# TemperatureACQ.net
KiCad netlist of a schematic drawn in Altium Designer
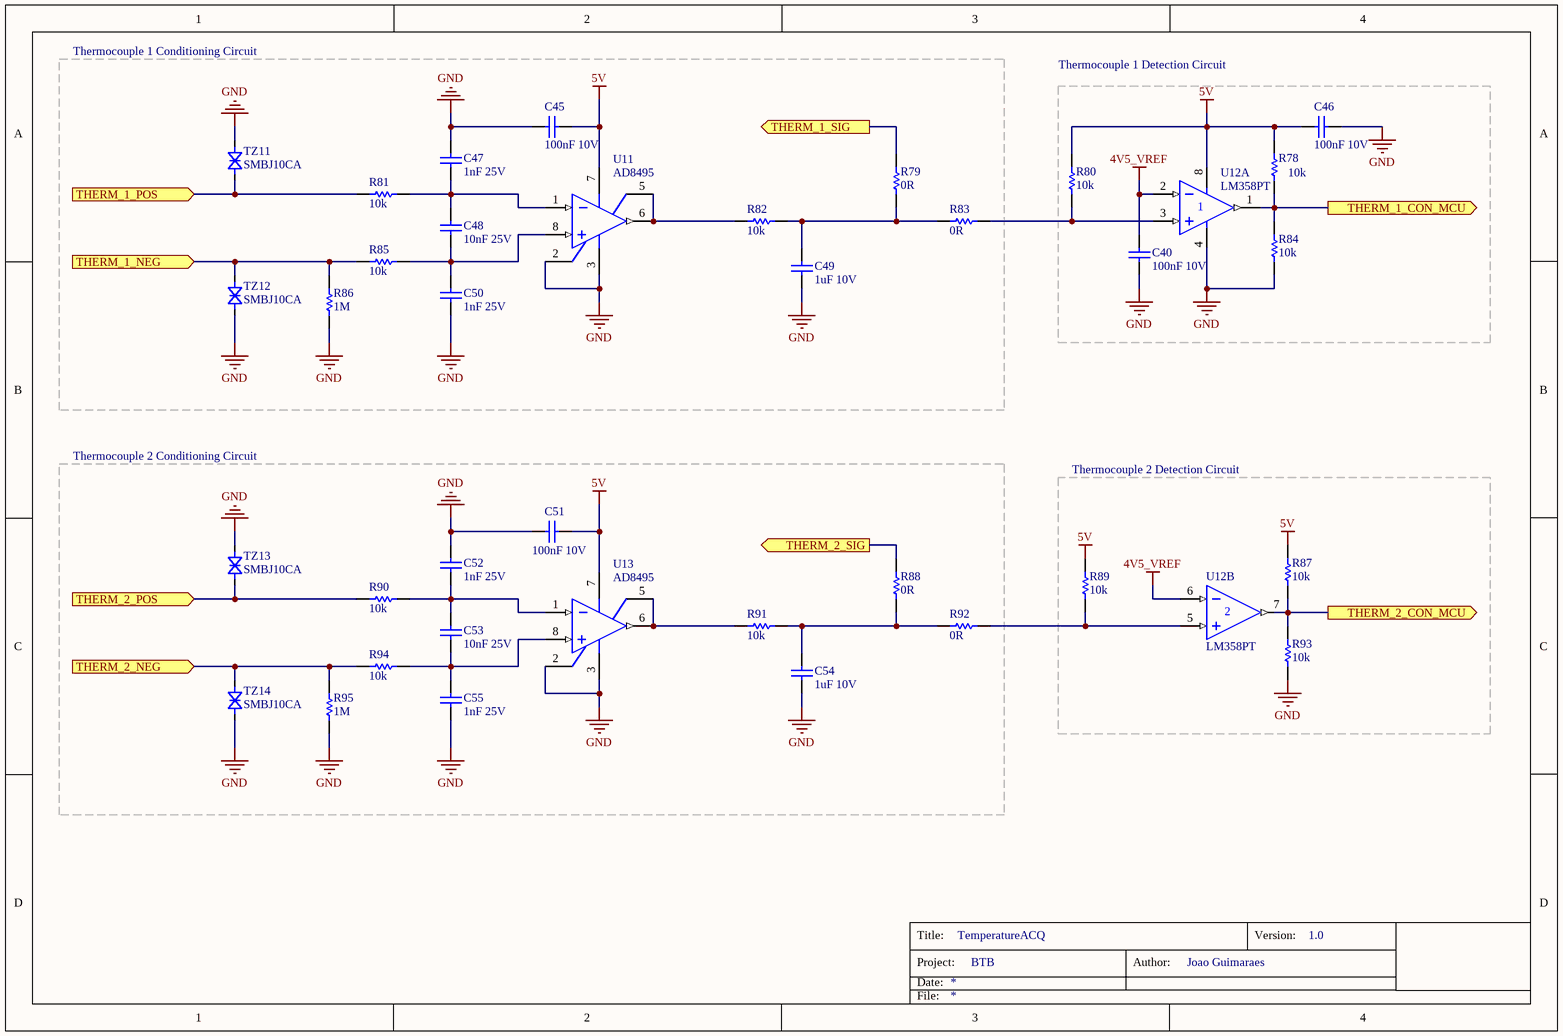
[diagram p0: TemperatureACQ.SchDoc]

(export (version "E")
  (design (tool "Eeschema 10.0.6"))
  (components
    (comp (ref "C40")
      (value "100nF 10V")
      (footprint "0402")
      (description "Capacitor")
      (fields (field (name "PARTNUMBER") "CAP.100n.10V.20%.SMD.0402") (field (name "MANUFACTURER") "Wurth"))
      (libsource (lib "IntLib") (part "Cap"))
    )
    (comp (ref "C45")
      (value "100nF 10V")
      (footprint "0402")
      (description "Capacitor")
      (fields (field (name "PARTNUMBER") "CAP.100n.10V.20%.SMD.0402") (field (name "MANUFACTURER") "Wurth"))
      (libsource (lib "IntLib") (part "Cap"))
    )
    (comp (ref "C46")
      (value "100nF 10V")
      (footprint "0402")
      (description "Capacitor")
      (fields (field (name "PARTNUMBER") "CAP.100n.10V.20%.SMD.0402") (field (name "MANUFACTURER") "Wurth"))
      (libsource (lib "IntLib") (part "Cap"))
    )
    (comp (ref "C47")
      (value "1nF 25V")
      (footprint "1608[0603]")
      (description "Capacitor")
      (fields (field (name "PARTNUMBER") "CAP.1n.25V.10%.SMD.0603") (field (name "MANUFACTURER") "Wurth"))
      (libsource (lib "IntLib") (part "Cap"))
    )
    (comp (ref "C48")
      (value "10nF 25V")
      (footprint "1608[0603]")
      (description "Capacitor")
      (fields (field (name "PARTNUMBER") "CAP.10n.25V.10%.SMD.0603") (field (name "MANUFACTURER") "Wurth"))
      (libsource (lib "IntLib") (part "Cap"))
    )
    (comp (ref "C49")
      (value "1uF 10V")
      (footprint "C0805")
      (description "Capacitor")
      (fields (field (name "PARTNUMBER") "CAP.1u.10V.10%.SMD.0805") (field (name "MANUFACTURER") "Vishay"))
      (libsource (lib "IntLib") (part "Cap"))
    )
    (comp (ref "C50")
      (value "1nF 25V")
      (footprint "1608[0603]")
      (description "Capacitor")
      (fields (field (name "PARTNUMBER") "CAP.1n.25V.10%.SMD.0603") (field (name "MANUFACTURER") "Vishay"))
      (libsource (lib "IntLib") (part "Cap"))
    )
    (comp (ref "C51")
      (value "100nF 10V")
      (footprint "0402")
      (description "Capacitor")
      (fields (field (name "PARTNUMBER") "CAP.100n.10V.20%.SMD.0402") (field (name "MANUFACTURER") "Wurth"))
      (libsource (lib "IntLib") (part "Cap"))
    )
    (comp (ref "C52")
      (value "1nF 25V")
      (footprint "1608[0603]")
      (description "Capacitor")
      (fields (field (name "PARTNUMBER") "CAP.1n.25V.10%.SMD.0603") (field (name "MANUFACTURER") "Vishay"))
      (libsource (lib "IntLib") (part "Cap"))
    )
    (comp (ref "C53")
      (value "10nF 25V")
      (footprint "1608[0603]")
      (description "Capacitor")
      (fields (field (name "PARTNUMBER") "CAP.10n.25V.10%.SMD.0603") (field (name "MANUFACTURER") "Wurth"))
      (libsource (lib "IntLib") (part "Cap"))
    )
    (comp (ref "C54")
      (value "1uF 10V")
      (footprint "C0805")
      (description "Capacitor")
      (fields (field (name "PARTNUMBER") "CAP.1u.10V.10%.SMD.0805") (field (name "MANUFACTURER") "Vishay"))
      (libsource (lib "IntLib") (part "Cap"))
    )
    (comp (ref "C55")
      (value "1nF 25V")
      (footprint "1608[0603]")
      (description "Capacitor")
      (fields (field (name "PARTNUMBER") "CAP.1n.25V.10%.SMD.0603") (field (name "MANUFACTURER") "Wurth"))
      (libsource (lib "IntLib") (part "Cap"))
    )
    (comp (ref "R78")
      (value "10k")
      (footprint "6-0805_M")
      (description "Resistor")
      (fields (field (name "PARTNUMBER") "RES.10K.1/8W.5%.SMD.0805") (field (name "MANUFACTURER") "Yageo"))
      (libsource (lib "IntLib") (part "Res"))
    )
    (comp (ref "R79")
      (value "0R")
      (footprint "6-0805_M")
      (description "Resistor")
      (fields (field (name "PARTNUMBER") "RES.0R.1/8W.5%.SMD.0805") (field (name "MANUFACTURER") "Vishay"))
      (libsource (lib "IntLib") (part "Res"))
    )
    (comp (ref "R80")
      (value "10k")
      (footprint "6-0805_M")
      (description "Resistor")
      (fields (field (name "PARTNUMBER") "RES.10k.1/8W.5%.SMD.0805") (field (name "MANUFACTURER") "Bourns"))
      (libsource (lib "IntLib") (part "Res"))
    )
    (comp (ref "R81")
      (value "10k")
      (footprint "6-0805_M")
      (description "Resistor")
      (fields (field (name "PARTNUMBER") "RES.10K.1/8W.5%.SMD.0805") (field (name "MANUFACTURER") "Yageo"))
      (libsource (lib "IntLib") (part "Res"))
    )
    (comp (ref "R82")
      (value "10k")
      (footprint "6-0805_M")
      (description "Resistor")
      (fields (field (name "PARTNUMBER") "RES.10K.1/8W.5%.SMD.0805") (field (name "MANUFACTURER") "Yageo"))
      (libsource (lib "IntLib") (part "Res"))
    )
    (comp (ref "R83")
      (value "0R")
      (footprint "6-0805_M")
      (description "Resistor")
      (fields (field (name "PARTNUMBER") "RES.0R.1/8W.5%.SMD.0805") (field (name "MANUFACTURER") "Vishay"))
      (libsource (lib "IntLib") (part "Res"))
    )
    (comp (ref "R84")
      (value "10k")
      (footprint "6-0805_M")
      (description "Resistor")
      (fields (field (name "PARTNUMBER") "RES.10K.1/8W.5%.SMD.0805") (field (name "MANUFACTURER") "Yageo"))
      (libsource (lib "IntLib") (part "Res"))
    )
    (comp (ref "R85")
      (value "10k")
      (footprint "6-0805_M")
      (description "Resistor")
      (fields (field (name "PARTNUMBER") "RES.10K.1/8W.5%.SMD.0805") (field (name "MANUFACTURER") "Yageo"))
      (libsource (lib "IntLib") (part "Res"))
    )
    (comp (ref "R86")
      (value "1M")
      (footprint "6-0805_M")
      (description "Resistor")
      (fields (field (name "PARTNUMBER") "RES.1M.1/8W.5%.SMD.0805") (field (name "MANUFACTURER") "Bourns"))
      (libsource (lib "IntLib") (part "Res"))
    )
    (comp (ref "R87")
      (value "10k")
      (footprint "6-0805_M")
      (description "Resistor")
      (fields (field (name "PARTNUMBER") "RES.10K.1/8W.5%.SMD.0805") (field (name "MANUFACTURER") "Yageo"))
      (libsource (lib "IntLib") (part "Res"))
    )
    (comp (ref "R88")
      (value "0R")
      (footprint "6-0805_M")
      (description "Resistor")
      (fields (field (name "PARTNUMBER") "RES.0R.1/8W.5%.SMD.0805") (field (name "MANUFACTURER") "Vishay"))
      (libsource (lib "IntLib") (part "Res"))
    )
    (comp (ref "R89")
      (value "10k")
      (footprint "6-0805_M")
      (description "Resistor")
      (fields (field (name "PARTNUMBER") "RES.10k.1/8W.5%.SMD.0805") (field (name "MANUFACTURER") "Bourns"))
      (libsource (lib "IntLib") (part "Res"))
    )
    (comp (ref "R90")
      (value "10k")
      (footprint "6-0805_M")
      (description "Resistor")
      (fields (field (name "PARTNUMBER") "RES.10K.1/8W.5%.SMD.0805") (field (name "MANUFACTURER") "Yageo"))
      (libsource (lib "IntLib") (part "Res"))
    )
    (comp (ref "R91")
      (value "10k")
      (footprint "6-0805_M")
      (description "Resistor")
      (fields (field (name "PARTNUMBER") "RES.10K.1/8W.5%.SMD.0805") (field (name "MANUFACTURER") "Yageo"))
      (libsource (lib "IntLib") (part "Res"))
    )
    (comp (ref "R92")
      (value "0R")
      (footprint "6-0805_M")
      (description "Resistor")
      (fields (field (name "PARTNUMBER") "RES.0R.1/8W.5%.SMD.0805") (field (name "MANUFACTURER") "Vishay"))
      (libsource (lib "IntLib") (part "Res"))
    )
    (comp (ref "R93")
      (value "10k")
      (footprint "6-0805_M")
      (description "Resistor")
      (fields (field (name "PARTNUMBER") "RES.10K.1/8W.5%.SMD.0805") (field (name "MANUFACTURER") "Yageo"))
      (libsource (lib "IntLib") (part "Res"))
    )
    (comp (ref "R94")
      (value "10k")
      (footprint "6-0805_M")
      (description "Resistor")
      (fields (field (name "PARTNUMBER") "RES.10K.1/8W.5%.SMD.0805") (field (name "MANUFACTURER") "Yageo"))
      (libsource (lib "IntLib") (part "Res"))
    )
    (comp (ref "R95")
      (value "1M")
      (footprint "6-0805_M")
      (description "Resistor")
      (fields (field (name "PARTNUMBER") "RES.1M.1/8W.5%.SMD.0805") (field (name "MANUFACTURER") "Bourns"))
      (libsource (lib "IntLib") (part "Res"))
    )
    (comp (ref "TZ11")
      (value "SMBJ10CA")
      (footprint "DO-214AA")
      (description "ESD Suppressors / TVS Diodes 600W 10.0V")
      (fields (field (name "PARTNUMBER") "SMBJ10CA-13-F") (field (name "MANUFACTURER") "Diodes"))
      (libsource (lib "IntLib") (part "SMBJ10CA"))
    )
    (comp (ref "TZ12")
      (value "SMBJ10CA")
      (footprint "DO-214AA")
      (description "ESD Suppressors / TVS Diodes 600W 10.0V")
      (fields (field (name "PARTNUMBER") "SMBJ10CA-13-F") (field (name "MANUFACTURER") "Diodes"))
      (libsource (lib "IntLib") (part "SMBJ10CA"))
    )
    (comp (ref "TZ13")
      (value "SMBJ10CA")
      (footprint "DO-214AA")
      (description "ESD Suppressors / TVS Diodes 600W 10.0V")
      (fields (field (name "PARTNUMBER") "SMBJ10CA-13-F") (field (name "MANUFACTURER") "Diodes"))
      (libsource (lib "IntLib") (part "SMBJ10CA"))
    )
    (comp (ref "TZ14")
      (value "SMBJ10CA")
      (footprint "DO-214AA")
      (description "ESD Suppressors / TVS Diodes 600W 10.0V")
      (fields (field (name "PARTNUMBER") "SMBJ10CA-13-F") (field (name "MANUFACTURER") "Diodes"))
      (libsource (lib "IntLib") (part "SMBJ10CA"))
    )
    (comp (ref "U11")
      (value "AD8495")
      (footprint "RM_8")
      (description "Precision Type K Thermocouple Amplifier with Cold Junction Compensation")
      (fields (field (name "PARTNUMBER") "AD8495CRMZ-R7") (field (name "MANUFACTURER") "Analog Devices"))
      (libsource (lib "IntLib") (part "AD8495"))
    )
    (comp (ref "U12")
      (value "LM358PT")
      (footprint "TSOP-8")
      (description "Operational Amplifiers - Op Amps Dual Low Power")
      (fields (field (name "MANUFACTURER") "STMicroelectronics"))
      (libsource (lib "IntLib") (part "LM358PT"))
    )
    (comp (ref "U13")
      (value "AD8495")
      (footprint "RM_8")
      (description "Precision Type K Thermocouple Amplifier with Cold Junction Compensation")
      (fields (field (name "PARTNUMBER") "AD8495CRMZ-R7") (field (name "MANUFACTURER") "Analog Devices"))
      (libsource (lib "IntLib") (part "AD8495"))
    )
  )
  (nets
    (net (code "1") (name "/THERM_1_CON_MCU") (class "Default")
      (node (ref "R78") (pin "2") (pinfunction "2_2") (pintype "passive"))
      (node (ref "R84") (pin "1") (pinfunction "1_1") (pintype "passive"))
      (node (ref "U12") (pin "1") (pinfunction "OUT_1") (pintype "output"))
    )
    (net (code "2") (name "/THERM_1_NEG") (class "Default")
      (node (ref "R85") (pin "1") (pinfunction "1_1") (pintype "passive"))
      (node (ref "R86") (pin "2") (pinfunction "2_2") (pintype "passive"))
      (node (ref "TZ12") (pin "2") (pinfunction "A_2") (pintype "passive"))
    )
    (net (code "3") (name "/THERM_1_POS") (class "Default")
      (node (ref "R81") (pin "1") (pinfunction "1_1") (pintype "passive"))
      (node (ref "TZ11") (pin "1") (pinfunction "C_1") (pintype "passive"))
    )
    (net (code "4") (name "/THERM_1_SIG") (class "Default")
      (node (ref "R79") (pin "1") (pinfunction "1_1") (pintype "passive"))
    )
    (net (code "5") (name "/THERM_2_CON_MCU") (class "Default")
      (node (ref "R87") (pin "2") (pinfunction "2_2") (pintype "passive"))
      (node (ref "R93") (pin "1") (pinfunction "1_1") (pintype "passive"))
      (node (ref "U12") (pin "7") (pinfunction "OUT_7") (pintype "output"))
    )
    (net (code "6") (name "/THERM_2_NEG") (class "Default")
      (node (ref "R94") (pin "1") (pinfunction "1_1") (pintype "passive"))
      (node (ref "R95") (pin "2") (pinfunction "2_2") (pintype "passive"))
      (node (ref "TZ14") (pin "2") (pinfunction "A_2") (pintype "passive"))
    )
    (net (code "7") (name "/THERM_2_POS") (class "Default")
      (node (ref "R90") (pin "1") (pinfunction "1_1") (pintype "passive"))
      (node (ref "TZ13") (pin "1") (pinfunction "C_1") (pintype "passive"))
    )
    (net (code "8") (name "/THERM_2_SIG") (class "Default")
      (node (ref "R88") (pin "1") (pinfunction "1_1") (pintype "passive"))
    )
    (net (code "9") (name "4V5_VREF") (class "Default")
      (node (ref "C40") (pin "2") (pinfunction "2_2") (pintype "passive"))
      (node (ref "U12") (pin "2") (pinfunction "IN-_2") (pintype "input"))
      (node (ref "U12") (pin "6") (pinfunction "IN-_6") (pintype "input"))
    )
    (net (code "10") (name "5V") (class "Default")
      (node (ref "C45") (pin "2") (pinfunction "2_2") (pintype "passive"))
      (node (ref "C46") (pin "2") (pinfunction "2_2") (pintype "passive"))
      (node (ref "C51") (pin "2") (pinfunction "2_2") (pintype "passive"))
      (node (ref "R78") (pin "1") (pinfunction "1_1") (pintype "passive"))
      (node (ref "R80") (pin "1") (pinfunction "1_1") (pintype "passive"))
      (node (ref "R87") (pin "1") (pinfunction "1_1") (pintype "passive"))
      (node (ref "R89") (pin "1") (pinfunction "1_1") (pintype "passive"))
      (node (ref "U11") (pin "7") (pinfunction "V+_7") (pintype "power_in"))
      (node (ref "U12") (pin "8") (pinfunction "Vs+_8") (pintype "passive"))
      (node (ref "U13") (pin "7") (pinfunction "V+_7") (pintype "power_in"))
    )
    (net (code "11") (name "GND") (class "Default")
      (node (ref "C40") (pin "1") (pinfunction "1_1") (pintype "passive"))
      (node (ref "C45") (pin "1") (pinfunction "1_1") (pintype "passive"))
      (node (ref "C46") (pin "1") (pinfunction "1_1") (pintype "passive"))
      (node (ref "C47") (pin "2") (pinfunction "2_2") (pintype "passive"))
      (node (ref "C49") (pin "1") (pinfunction "1_1") (pintype "passive"))
      (node (ref "C50") (pin "1") (pinfunction "1_1") (pintype "passive"))
      (node (ref "C51") (pin "1") (pinfunction "1_1") (pintype "passive"))
      (node (ref "C52") (pin "2") (pinfunction "2_2") (pintype "passive"))
      (node (ref "C54") (pin "1") (pinfunction "1_1") (pintype "passive"))
      (node (ref "C55") (pin "1") (pinfunction "1_1") (pintype "passive"))
      (node (ref "R84") (pin "2") (pinfunction "2_2") (pintype "passive"))
      (node (ref "R86") (pin "1") (pinfunction "1_1") (pintype "passive"))
      (node (ref "R93") (pin "2") (pinfunction "2_2") (pintype "passive"))
      (node (ref "R95") (pin "1") (pinfunction "1_1") (pintype "passive"))
      (node (ref "TZ11") (pin "2") (pinfunction "A_2") (pintype "passive"))
      (node (ref "TZ12") (pin "1") (pinfunction "C_1") (pintype "passive"))
      (node (ref "TZ13") (pin "2") (pinfunction "A_2") (pintype "passive"))
      (node (ref "TZ14") (pin "1") (pinfunction "C_1") (pintype "passive"))
      (node (ref "U11") (pin "2") (pinfunction "REF_2") (pintype "passive"))
      (node (ref "U11") (pin "3") (pinfunction "V-_3") (pintype "power_in"))
      (node (ref "U12") (pin "4") (pinfunction "Vs-_4") (pintype "passive"))
      (node (ref "U13") (pin "2") (pinfunction "REF_2") (pintype "passive"))
      (node (ref "U13") (pin "3") (pinfunction "V-_3") (pintype "power_in"))
    )
    (net (code "12") (name "Net-(C49-Pad2)") (class "Default")
      (node (ref "C49") (pin "2") (pinfunction "2_2") (pintype "passive"))
      (node (ref "R79") (pin "2") (pinfunction "2_2") (pintype "passive"))
      (node (ref "R82") (pin "1") (pinfunction "1_1") (pintype "passive"))
      (node (ref "R83") (pin "1") (pinfunction "1_1") (pintype "passive"))
    )
    (net (code "13") (name "Net-(C54-Pad2)") (class "Default")
      (node (ref "C54") (pin "2") (pinfunction "2_2") (pintype "passive"))
      (node (ref "R88") (pin "2") (pinfunction "2_2") (pintype "passive"))
      (node (ref "R91") (pin "1") (pinfunction "1_1") (pintype "passive"))
      (node (ref "R92") (pin "1") (pinfunction "1_1") (pintype "passive"))
    )
    (net (code "14") (name "Net-(U11-IN+)") (class "Default")
      (node (ref "C48") (pin "1") (pinfunction "1_1") (pintype "passive"))
      (node (ref "C50") (pin "2") (pinfunction "2_2") (pintype "passive"))
      (node (ref "R85") (pin "2") (pinfunction "2_2") (pintype "passive"))
      (node (ref "U11") (pin "8") (pinfunction "IN+_8") (pintype "input"))
    )
    (net (code "15") (name "Net-(U11-IN-)") (class "Default")
      (node (ref "C47") (pin "1") (pinfunction "1_1") (pintype "passive"))
      (node (ref "C48") (pin "2") (pinfunction "2_2") (pintype "passive"))
      (node (ref "R81") (pin "2") (pinfunction "2_2") (pintype "passive"))
      (node (ref "U11") (pin "1") (pinfunction "IN-_1") (pintype "input"))
    )
    (net (code "16") (name "Net-(U11-OUT)") (class "Default")
      (node (ref "R82") (pin "2") (pinfunction "2_2") (pintype "passive"))
      (node (ref "U11") (pin "5") (pinfunction "SENSE_5") (pintype "passive"))
      (node (ref "U11") (pin "6") (pinfunction "OUT_6") (pintype "output"))
    )
    (net (code "17") (name "Net-(U12A-IN+)") (class "Default")
      (node (ref "R80") (pin "2") (pinfunction "2_2") (pintype "passive"))
      (node (ref "R83") (pin "2") (pinfunction "2_2") (pintype "passive"))
      (node (ref "U12") (pin "3") (pinfunction "IN+_3") (pintype "input"))
    )
    (net (code "18") (name "Net-(U12B-IN+)") (class "Default")
      (node (ref "R89") (pin "2") (pinfunction "2_2") (pintype "passive"))
      (node (ref "R92") (pin "2") (pinfunction "2_2") (pintype "passive"))
      (node (ref "U12") (pin "5") (pinfunction "IN+_5") (pintype "input"))
    )
    (net (code "19") (name "Net-(U13-IN+)") (class "Default")
      (node (ref "C53") (pin "1") (pinfunction "1_1") (pintype "passive"))
      (node (ref "C55") (pin "2") (pinfunction "2_2") (pintype "passive"))
      (node (ref "R94") (pin "2") (pinfunction "2_2") (pintype "passive"))
      (node (ref "U13") (pin "8") (pinfunction "IN+_8") (pintype "input"))
    )
    (net (code "20") (name "Net-(U13-IN-)") (class "Default")
      (node (ref "C52") (pin "1") (pinfunction "1_1") (pintype "passive"))
      (node (ref "C53") (pin "2") (pinfunction "2_2") (pintype "passive"))
      (node (ref "R90") (pin "2") (pinfunction "2_2") (pintype "passive"))
      (node (ref "U13") (pin "1") (pinfunction "IN-_1") (pintype "input"))
    )
    (net (code "21") (name "Net-(U13-OUT)") (class "Default")
      (node (ref "R91") (pin "2") (pinfunction "2_2") (pintype "passive"))
      (node (ref "U13") (pin "5") (pinfunction "SENSE_5") (pintype "passive"))
      (node (ref "U13") (pin "6") (pinfunction "OUT_6") (pintype "output"))
    )
  )
)
